# CANFD_HUB.net
KiCad netlist of a schematic drawn in EAGLE
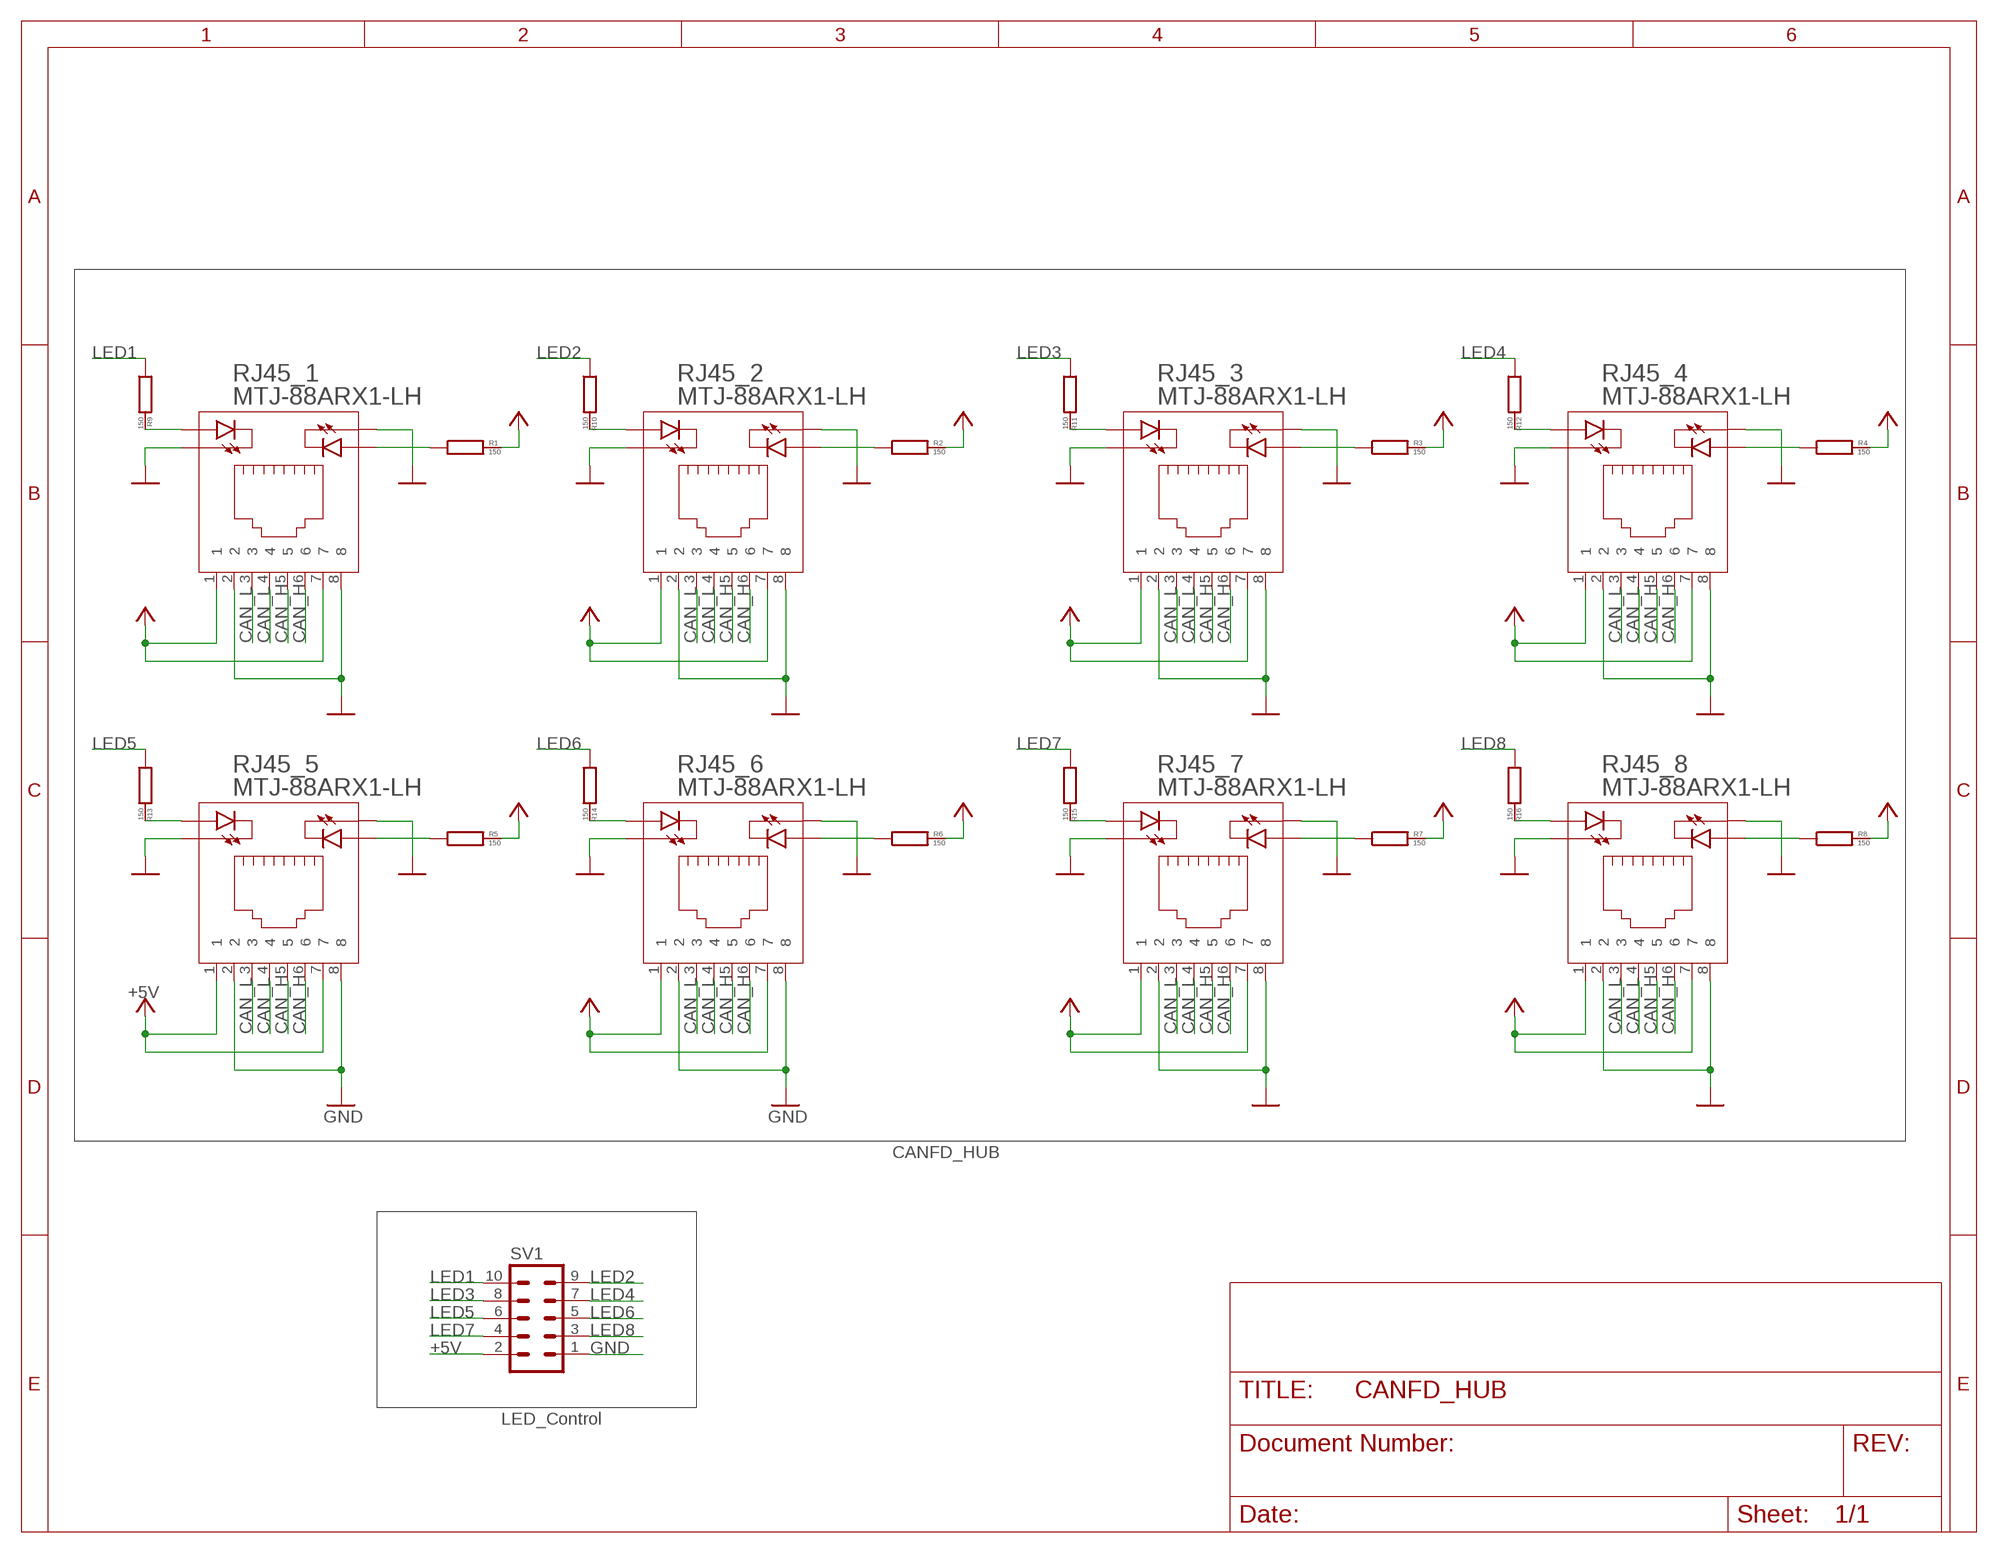
[diagram p0: schematic, sheet 1]

(export (version "E")
  (design (tool "Eeschema 10.0.6"))
  (components
    (comp (ref "R1")
      (value "150")
      (footprint "eagle-import:CR0603")
      (libsource (lib "eagle-import") (part "CR0603"))
    )
    (comp (ref "R2")
      (value "150")
      (footprint "eagle-import:CR0603")
      (libsource (lib "eagle-import") (part "CR0603"))
    )
    (comp (ref "R3")
      (value "150")
      (footprint "eagle-import:CR0603")
      (libsource (lib "eagle-import") (part "CR0603"))
    )
    (comp (ref "R4")
      (value "150")
      (footprint "eagle-import:CR0603")
      (libsource (lib "eagle-import") (part "CR0603"))
    )
    (comp (ref "R5")
      (value "150")
      (footprint "eagle-import:CR0603")
      (libsource (lib "eagle-import") (part "CR0603"))
    )
    (comp (ref "R6")
      (value "150")
      (footprint "eagle-import:CR0603")
      (libsource (lib "eagle-import") (part "CR0603"))
    )
    (comp (ref "R7")
      (value "150")
      (footprint "eagle-import:CR0603")
      (libsource (lib "eagle-import") (part "CR0603"))
    )
    (comp (ref "R8")
      (value "150")
      (footprint "eagle-import:CR0603")
      (libsource (lib "eagle-import") (part "CR0603"))
    )
    (comp (ref "R9")
      (value "150")
      (footprint "eagle-import:CR0603")
      (libsource (lib "eagle-import") (part "CR0603"))
    )
    (comp (ref "R10")
      (value "150")
      (footprint "eagle-import:CR0603")
      (libsource (lib "eagle-import") (part "CR0603"))
    )
    (comp (ref "R11")
      (value "150")
      (footprint "eagle-import:CR0603")
      (libsource (lib "eagle-import") (part "CR0603"))
    )
    (comp (ref "R12")
      (value "150")
      (footprint "eagle-import:CR0603")
      (libsource (lib "eagle-import") (part "CR0603"))
    )
    (comp (ref "R13")
      (value "150")
      (footprint "eagle-import:CR0603")
      (libsource (lib "eagle-import") (part "CR0603"))
    )
    (comp (ref "R14")
      (value "150")
      (footprint "eagle-import:CR0603")
      (libsource (lib "eagle-import") (part "CR0603"))
    )
    (comp (ref "R15")
      (value "150")
      (footprint "eagle-import:CR0603")
      (libsource (lib "eagle-import") (part "CR0603"))
    )
    (comp (ref "R16")
      (value "150")
      (footprint "eagle-import:CR0603")
      (libsource (lib "eagle-import") (part "CR0603"))
    )
    (comp (ref "RJ45_1")
      (value "MTJ-88ARX1-LH")
      (footprint "eagle-import:MTJ-88ARX1-LH")
      (libsource (lib "eagle-import") (part "MTJ-88ARX1-LH"))
    )
    (comp (ref "RJ45_2")
      (value "MTJ-88ARX1-LH")
      (footprint "eagle-import:MTJ-88ARX1-LH")
      (libsource (lib "eagle-import") (part "MTJ-88ARX1-LH"))
    )
    (comp (ref "RJ45_3")
      (value "MTJ-88ARX1-LH")
      (footprint "eagle-import:MTJ-88ARX1-LH")
      (libsource (lib "eagle-import") (part "MTJ-88ARX1-LH"))
    )
    (comp (ref "RJ45_4")
      (value "MTJ-88ARX1-LH")
      (footprint "eagle-import:MTJ-88ARX1-LH")
      (libsource (lib "eagle-import") (part "MTJ-88ARX1-LH"))
    )
    (comp (ref "RJ45_5")
      (value "MTJ-88ARX1-LH")
      (footprint "eagle-import:MTJ-88ARX1-LH")
      (libsource (lib "eagle-import") (part "MTJ-88ARX1-LH"))
    )
    (comp (ref "RJ45_6")
      (value "MTJ-88ARX1-LH")
      (footprint "eagle-import:MTJ-88ARX1-LH")
      (libsource (lib "eagle-import") (part "MTJ-88ARX1-LH"))
    )
    (comp (ref "RJ45_7")
      (value "MTJ-88ARX1-LH")
      (footprint "eagle-import:MTJ-88ARX1-LH")
      (libsource (lib "eagle-import") (part "MTJ-88ARX1-LH"))
    )
    (comp (ref "RJ45_8")
      (value "MTJ-88ARX1-LH")
      (footprint "eagle-import:MTJ-88ARX1-LH")
      (libsource (lib "eagle-import") (part "MTJ-88ARX1-LH"))
    )
    (comp (ref "SV1")
      (value "ML10")
      (footprint "eagle-import:ML10")
      (libsource (lib "eagle-import") (part "ML10"))
    )
  )
  (nets
    (net (code "1") (name "+5V") (class "Default")
      (node (ref "R1") (pin "RIGHT") (pinfunction "RIGHT_RIGHT") (pintype "bidirectional"))
      (node (ref "R2") (pin "RIGHT") (pinfunction "RIGHT_RIGHT") (pintype "bidirectional"))
      (node (ref "R3") (pin "RIGHT") (pinfunction "RIGHT_RIGHT") (pintype "bidirectional"))
      (node (ref "R4") (pin "RIGHT") (pinfunction "RIGHT_RIGHT") (pintype "bidirectional"))
      (node (ref "R5") (pin "RIGHT") (pinfunction "RIGHT_RIGHT") (pintype "bidirectional"))
      (node (ref "R6") (pin "RIGHT") (pinfunction "RIGHT_RIGHT") (pintype "bidirectional"))
      (node (ref "R7") (pin "RIGHT") (pinfunction "RIGHT_RIGHT") (pintype "bidirectional"))
      (node (ref "R8") (pin "RIGHT") (pinfunction "RIGHT_RIGHT") (pintype "bidirectional"))
      (node (ref "RJ45_1") (pin "1") (pinfunction "1_1") (pintype "bidirectional"))
      (node (ref "RJ45_1") (pin "7") (pinfunction "7_7") (pintype "bidirectional"))
      (node (ref "RJ45_2") (pin "1") (pinfunction "1_1") (pintype "bidirectional"))
      (node (ref "RJ45_2") (pin "7") (pinfunction "7_7") (pintype "bidirectional"))
      (node (ref "RJ45_3") (pin "1") (pinfunction "1_1") (pintype "bidirectional"))
      (node (ref "RJ45_3") (pin "7") (pinfunction "7_7") (pintype "bidirectional"))
      (node (ref "RJ45_4") (pin "1") (pinfunction "1_1") (pintype "bidirectional"))
      (node (ref "RJ45_4") (pin "7") (pinfunction "7_7") (pintype "bidirectional"))
      (node (ref "RJ45_5") (pin "1") (pinfunction "1_1") (pintype "bidirectional"))
      (node (ref "RJ45_5") (pin "7") (pinfunction "7_7") (pintype "bidirectional"))
      (node (ref "RJ45_6") (pin "1") (pinfunction "1_1") (pintype "bidirectional"))
      (node (ref "RJ45_6") (pin "7") (pinfunction "7_7") (pintype "bidirectional"))
      (node (ref "RJ45_7") (pin "1") (pinfunction "1_1") (pintype "bidirectional"))
      (node (ref "RJ45_7") (pin "7") (pinfunction "7_7") (pintype "bidirectional"))
      (node (ref "RJ45_8") (pin "1") (pinfunction "1_1") (pintype "bidirectional"))
      (node (ref "RJ45_8") (pin "7") (pinfunction "7_7") (pintype "bidirectional"))
      (node (ref "SV1") (pin "2") (pinfunction "2_2") (pintype "passive"))
    )
    (net (code "2") (name "/CAN_H") (class "Default")
      (node (ref "RJ45_1") (pin "5") (pinfunction "5_5") (pintype "bidirectional"))
      (node (ref "RJ45_1") (pin "6") (pinfunction "6_6") (pintype "bidirectional"))
      (node (ref "RJ45_2") (pin "5") (pinfunction "5_5") (pintype "bidirectional"))
      (node (ref "RJ45_2") (pin "6") (pinfunction "6_6") (pintype "bidirectional"))
      (node (ref "RJ45_3") (pin "5") (pinfunction "5_5") (pintype "bidirectional"))
      (node (ref "RJ45_3") (pin "6") (pinfunction "6_6") (pintype "bidirectional"))
      (node (ref "RJ45_4") (pin "5") (pinfunction "5_5") (pintype "bidirectional"))
      (node (ref "RJ45_4") (pin "6") (pinfunction "6_6") (pintype "bidirectional"))
      (node (ref "RJ45_5") (pin "5") (pinfunction "5_5") (pintype "bidirectional"))
      (node (ref "RJ45_5") (pin "6") (pinfunction "6_6") (pintype "bidirectional"))
      (node (ref "RJ45_6") (pin "5") (pinfunction "5_5") (pintype "bidirectional"))
      (node (ref "RJ45_6") (pin "6") (pinfunction "6_6") (pintype "bidirectional"))
      (node (ref "RJ45_7") (pin "5") (pinfunction "5_5") (pintype "bidirectional"))
      (node (ref "RJ45_7") (pin "6") (pinfunction "6_6") (pintype "bidirectional"))
      (node (ref "RJ45_8") (pin "5") (pinfunction "5_5") (pintype "bidirectional"))
      (node (ref "RJ45_8") (pin "6") (pinfunction "6_6") (pintype "bidirectional"))
    )
    (net (code "3") (name "/CAN_L") (class "Default")
      (node (ref "RJ45_1") (pin "3") (pinfunction "3_3") (pintype "bidirectional"))
      (node (ref "RJ45_1") (pin "4") (pinfunction "4_4") (pintype "bidirectional"))
      (node (ref "RJ45_2") (pin "3") (pinfunction "3_3") (pintype "bidirectional"))
      (node (ref "RJ45_2") (pin "4") (pinfunction "4_4") (pintype "bidirectional"))
      (node (ref "RJ45_3") (pin "3") (pinfunction "3_3") (pintype "bidirectional"))
      (node (ref "RJ45_3") (pin "4") (pinfunction "4_4") (pintype "bidirectional"))
      (node (ref "RJ45_4") (pin "3") (pinfunction "3_3") (pintype "bidirectional"))
      (node (ref "RJ45_4") (pin "4") (pinfunction "4_4") (pintype "bidirectional"))
      (node (ref "RJ45_5") (pin "3") (pinfunction "3_3") (pintype "bidirectional"))
      (node (ref "RJ45_5") (pin "4") (pinfunction "4_4") (pintype "bidirectional"))
      (node (ref "RJ45_6") (pin "3") (pinfunction "3_3") (pintype "bidirectional"))
      (node (ref "RJ45_6") (pin "4") (pinfunction "4_4") (pintype "bidirectional"))
      (node (ref "RJ45_7") (pin "3") (pinfunction "3_3") (pintype "bidirectional"))
      (node (ref "RJ45_7") (pin "4") (pinfunction "4_4") (pintype "bidirectional"))
      (node (ref "RJ45_8") (pin "3") (pinfunction "3_3") (pintype "bidirectional"))
      (node (ref "RJ45_8") (pin "4") (pinfunction "4_4") (pintype "bidirectional"))
    )
    (net (code "4") (name "/LED1") (class "Default")
      (node (ref "R9") (pin "LEFT") (pinfunction "LEFT_LEFT") (pintype "bidirectional"))
      (node (ref "SV1") (pin "10") (pinfunction "10_10") (pintype "passive"))
    )
    (net (code "5") (name "/LED2") (class "Default")
      (node (ref "R10") (pin "LEFT") (pinfunction "LEFT_LEFT") (pintype "bidirectional"))
      (node (ref "SV1") (pin "9") (pinfunction "9_9") (pintype "passive"))
    )
    (net (code "6") (name "/LED3") (class "Default")
      (node (ref "R11") (pin "LEFT") (pinfunction "LEFT_LEFT") (pintype "bidirectional"))
      (node (ref "SV1") (pin "8") (pinfunction "8_8") (pintype "passive"))
    )
    (net (code "7") (name "/LED4") (class "Default")
      (node (ref "R12") (pin "LEFT") (pinfunction "LEFT_LEFT") (pintype "bidirectional"))
      (node (ref "SV1") (pin "7") (pinfunction "7_7") (pintype "passive"))
    )
    (net (code "8") (name "/LED5") (class "Default")
      (node (ref "R13") (pin "LEFT") (pinfunction "LEFT_LEFT") (pintype "bidirectional"))
      (node (ref "SV1") (pin "6") (pinfunction "6_6") (pintype "passive"))
    )
    (net (code "9") (name "/LED6") (class "Default")
      (node (ref "R14") (pin "LEFT") (pinfunction "LEFT_LEFT") (pintype "bidirectional"))
      (node (ref "SV1") (pin "5") (pinfunction "5_5") (pintype "passive"))
    )
    (net (code "10") (name "/LED7") (class "Default")
      (node (ref "R15") (pin "LEFT") (pinfunction "LEFT_LEFT") (pintype "bidirectional"))
      (node (ref "SV1") (pin "4") (pinfunction "4_4") (pintype "passive"))
    )
    (net (code "11") (name "/LED8") (class "Default")
      (node (ref "R16") (pin "LEFT") (pinfunction "LEFT_LEFT") (pintype "bidirectional"))
      (node (ref "SV1") (pin "3") (pinfunction "3_3") (pintype "passive"))
    )
    (net (code "12") (name "GND") (class "Default")
      (node (ref "RJ45_1") (pin "2") (pinfunction "2_2") (pintype "bidirectional"))
      (node (ref "RJ45_1") (pin "8") (pinfunction "8_8") (pintype "bidirectional"))
      (node (ref "RJ45_1") (pin "LED1_K") (pinfunction "LED1_K_LED1_K") (pintype "bidirectional"))
      (node (ref "RJ45_1") (pin "LED2_K") (pinfunction "LED2_K_LED2_K") (pintype "bidirectional"))
      (node (ref "RJ45_2") (pin "2") (pinfunction "2_2") (pintype "bidirectional"))
      (node (ref "RJ45_2") (pin "8") (pinfunction "8_8") (pintype "bidirectional"))
      (node (ref "RJ45_2") (pin "LED1_K") (pinfunction "LED1_K_LED1_K") (pintype "bidirectional"))
      (node (ref "RJ45_2") (pin "LED2_K") (pinfunction "LED2_K_LED2_K") (pintype "bidirectional"))
      (node (ref "RJ45_3") (pin "2") (pinfunction "2_2") (pintype "bidirectional"))
      (node (ref "RJ45_3") (pin "8") (pinfunction "8_8") (pintype "bidirectional"))
      (node (ref "RJ45_3") (pin "LED1_K") (pinfunction "LED1_K_LED1_K") (pintype "bidirectional"))
      (node (ref "RJ45_3") (pin "LED2_K") (pinfunction "LED2_K_LED2_K") (pintype "bidirectional"))
      (node (ref "RJ45_4") (pin "2") (pinfunction "2_2") (pintype "bidirectional"))
      (node (ref "RJ45_4") (pin "8") (pinfunction "8_8") (pintype "bidirectional"))
      (node (ref "RJ45_4") (pin "LED1_K") (pinfunction "LED1_K_LED1_K") (pintype "bidirectional"))
      (node (ref "RJ45_4") (pin "LED2_K") (pinfunction "LED2_K_LED2_K") (pintype "bidirectional"))
      (node (ref "RJ45_5") (pin "2") (pinfunction "2_2") (pintype "bidirectional"))
      (node (ref "RJ45_5") (pin "8") (pinfunction "8_8") (pintype "bidirectional"))
      (node (ref "RJ45_5") (pin "LED1_K") (pinfunction "LED1_K_LED1_K") (pintype "bidirectional"))
      (node (ref "RJ45_5") (pin "LED2_K") (pinfunction "LED2_K_LED2_K") (pintype "bidirectional"))
      (node (ref "RJ45_6") (pin "2") (pinfunction "2_2") (pintype "bidirectional"))
      (node (ref "RJ45_6") (pin "8") (pinfunction "8_8") (pintype "bidirectional"))
      (node (ref "RJ45_6") (pin "LED1_K") (pinfunction "LED1_K_LED1_K") (pintype "bidirectional"))
      (node (ref "RJ45_6") (pin "LED2_K") (pinfunction "LED2_K_LED2_K") (pintype "bidirectional"))
      (node (ref "RJ45_7") (pin "2") (pinfunction "2_2") (pintype "bidirectional"))
      (node (ref "RJ45_7") (pin "8") (pinfunction "8_8") (pintype "bidirectional"))
      (node (ref "RJ45_7") (pin "LED1_K") (pinfunction "LED1_K_LED1_K") (pintype "bidirectional"))
      (node (ref "RJ45_7") (pin "LED2_K") (pinfunction "LED2_K_LED2_K") (pintype "bidirectional"))
      (node (ref "RJ45_8") (pin "2") (pinfunction "2_2") (pintype "bidirectional"))
      (node (ref "RJ45_8") (pin "8") (pinfunction "8_8") (pintype "bidirectional"))
      (node (ref "RJ45_8") (pin "LED1_K") (pinfunction "LED1_K_LED1_K") (pintype "bidirectional"))
      (node (ref "RJ45_8") (pin "LED2_K") (pinfunction "LED2_K_LED2_K") (pintype "bidirectional"))
      (node (ref "SV1") (pin "1") (pinfunction "1_1") (pintype "passive"))
    )
    (net (code "13") (name "Net-(R1-PadLEFT)") (class "Default")
      (node (ref "R1") (pin "LEFT") (pinfunction "LEFT_LEFT") (pintype "bidirectional"))
      (node (ref "RJ45_1") (pin "LED2_A") (pinfunction "LED2_A_LED2_A") (pintype "bidirectional"))
    )
    (net (code "14") (name "Net-(R2-PadLEFT)") (class "Default")
      (node (ref "R2") (pin "LEFT") (pinfunction "LEFT_LEFT") (pintype "bidirectional"))
      (node (ref "RJ45_2") (pin "LED2_A") (pinfunction "LED2_A_LED2_A") (pintype "bidirectional"))
    )
    (net (code "15") (name "Net-(R3-PadLEFT)") (class "Default")
      (node (ref "R3") (pin "LEFT") (pinfunction "LEFT_LEFT") (pintype "bidirectional"))
      (node (ref "RJ45_3") (pin "LED2_A") (pinfunction "LED2_A_LED2_A") (pintype "bidirectional"))
    )
    (net (code "16") (name "Net-(R4-PadLEFT)") (class "Default")
      (node (ref "R4") (pin "LEFT") (pinfunction "LEFT_LEFT") (pintype "bidirectional"))
      (node (ref "RJ45_4") (pin "LED2_A") (pinfunction "LED2_A_LED2_A") (pintype "bidirectional"))
    )
    (net (code "17") (name "Net-(R5-PadLEFT)") (class "Default")
      (node (ref "R5") (pin "LEFT") (pinfunction "LEFT_LEFT") (pintype "bidirectional"))
      (node (ref "RJ45_5") (pin "LED2_A") (pinfunction "LED2_A_LED2_A") (pintype "bidirectional"))
    )
    (net (code "18") (name "Net-(R6-PadLEFT)") (class "Default")
      (node (ref "R6") (pin "LEFT") (pinfunction "LEFT_LEFT") (pintype "bidirectional"))
      (node (ref "RJ45_6") (pin "LED2_A") (pinfunction "LED2_A_LED2_A") (pintype "bidirectional"))
    )
    (net (code "19") (name "Net-(R7-PadLEFT)") (class "Default")
      (node (ref "R7") (pin "LEFT") (pinfunction "LEFT_LEFT") (pintype "bidirectional"))
      (node (ref "RJ45_7") (pin "LED2_A") (pinfunction "LED2_A_LED2_A") (pintype "bidirectional"))
    )
    (net (code "20") (name "Net-(R8-PadLEFT)") (class "Default")
      (node (ref "R8") (pin "LEFT") (pinfunction "LEFT_LEFT") (pintype "bidirectional"))
      (node (ref "RJ45_8") (pin "LED2_A") (pinfunction "LED2_A_LED2_A") (pintype "bidirectional"))
    )
    (net (code "21") (name "Net-(R9-PadRIGHT)") (class "Default")
      (node (ref "R9") (pin "RIGHT") (pinfunction "RIGHT_RIGHT") (pintype "bidirectional"))
      (node (ref "RJ45_1") (pin "LED1_A") (pinfunction "LED1_A_LED1_A") (pintype "bidirectional"))
    )
    (net (code "22") (name "Net-(R10-PadRIGHT)") (class "Default")
      (node (ref "R10") (pin "RIGHT") (pinfunction "RIGHT_RIGHT") (pintype "bidirectional"))
      (node (ref "RJ45_2") (pin "LED1_A") (pinfunction "LED1_A_LED1_A") (pintype "bidirectional"))
    )
    (net (code "23") (name "Net-(R11-PadRIGHT)") (class "Default")
      (node (ref "R11") (pin "RIGHT") (pinfunction "RIGHT_RIGHT") (pintype "bidirectional"))
      (node (ref "RJ45_3") (pin "LED1_A") (pinfunction "LED1_A_LED1_A") (pintype "bidirectional"))
    )
    (net (code "24") (name "Net-(R12-PadRIGHT)") (class "Default")
      (node (ref "R12") (pin "RIGHT") (pinfunction "RIGHT_RIGHT") (pintype "bidirectional"))
      (node (ref "RJ45_4") (pin "LED1_A") (pinfunction "LED1_A_LED1_A") (pintype "bidirectional"))
    )
    (net (code "25") (name "Net-(R13-PadRIGHT)") (class "Default")
      (node (ref "R13") (pin "RIGHT") (pinfunction "RIGHT_RIGHT") (pintype "bidirectional"))
      (node (ref "RJ45_5") (pin "LED1_A") (pinfunction "LED1_A_LED1_A") (pintype "bidirectional"))
    )
    (net (code "26") (name "Net-(R14-PadRIGHT)") (class "Default")
      (node (ref "R14") (pin "RIGHT") (pinfunction "RIGHT_RIGHT") (pintype "bidirectional"))
      (node (ref "RJ45_6") (pin "LED1_A") (pinfunction "LED1_A_LED1_A") (pintype "bidirectional"))
    )
    (net (code "27") (name "Net-(R15-PadRIGHT)") (class "Default")
      (node (ref "R15") (pin "RIGHT") (pinfunction "RIGHT_RIGHT") (pintype "bidirectional"))
      (node (ref "RJ45_7") (pin "LED1_A") (pinfunction "LED1_A_LED1_A") (pintype "bidirectional"))
    )
    (net (code "28") (name "Net-(R16-PadRIGHT)") (class "Default")
      (node (ref "R16") (pin "RIGHT") (pinfunction "RIGHT_RIGHT") (pintype "bidirectional"))
      (node (ref "RJ45_8") (pin "LED1_A") (pinfunction "LED1_A_LED1_A") (pintype "bidirectional"))
    )
  )
)
